# v2-carb-sync-shield.net
KiCad netlist of a schematic drawn in EAGLE
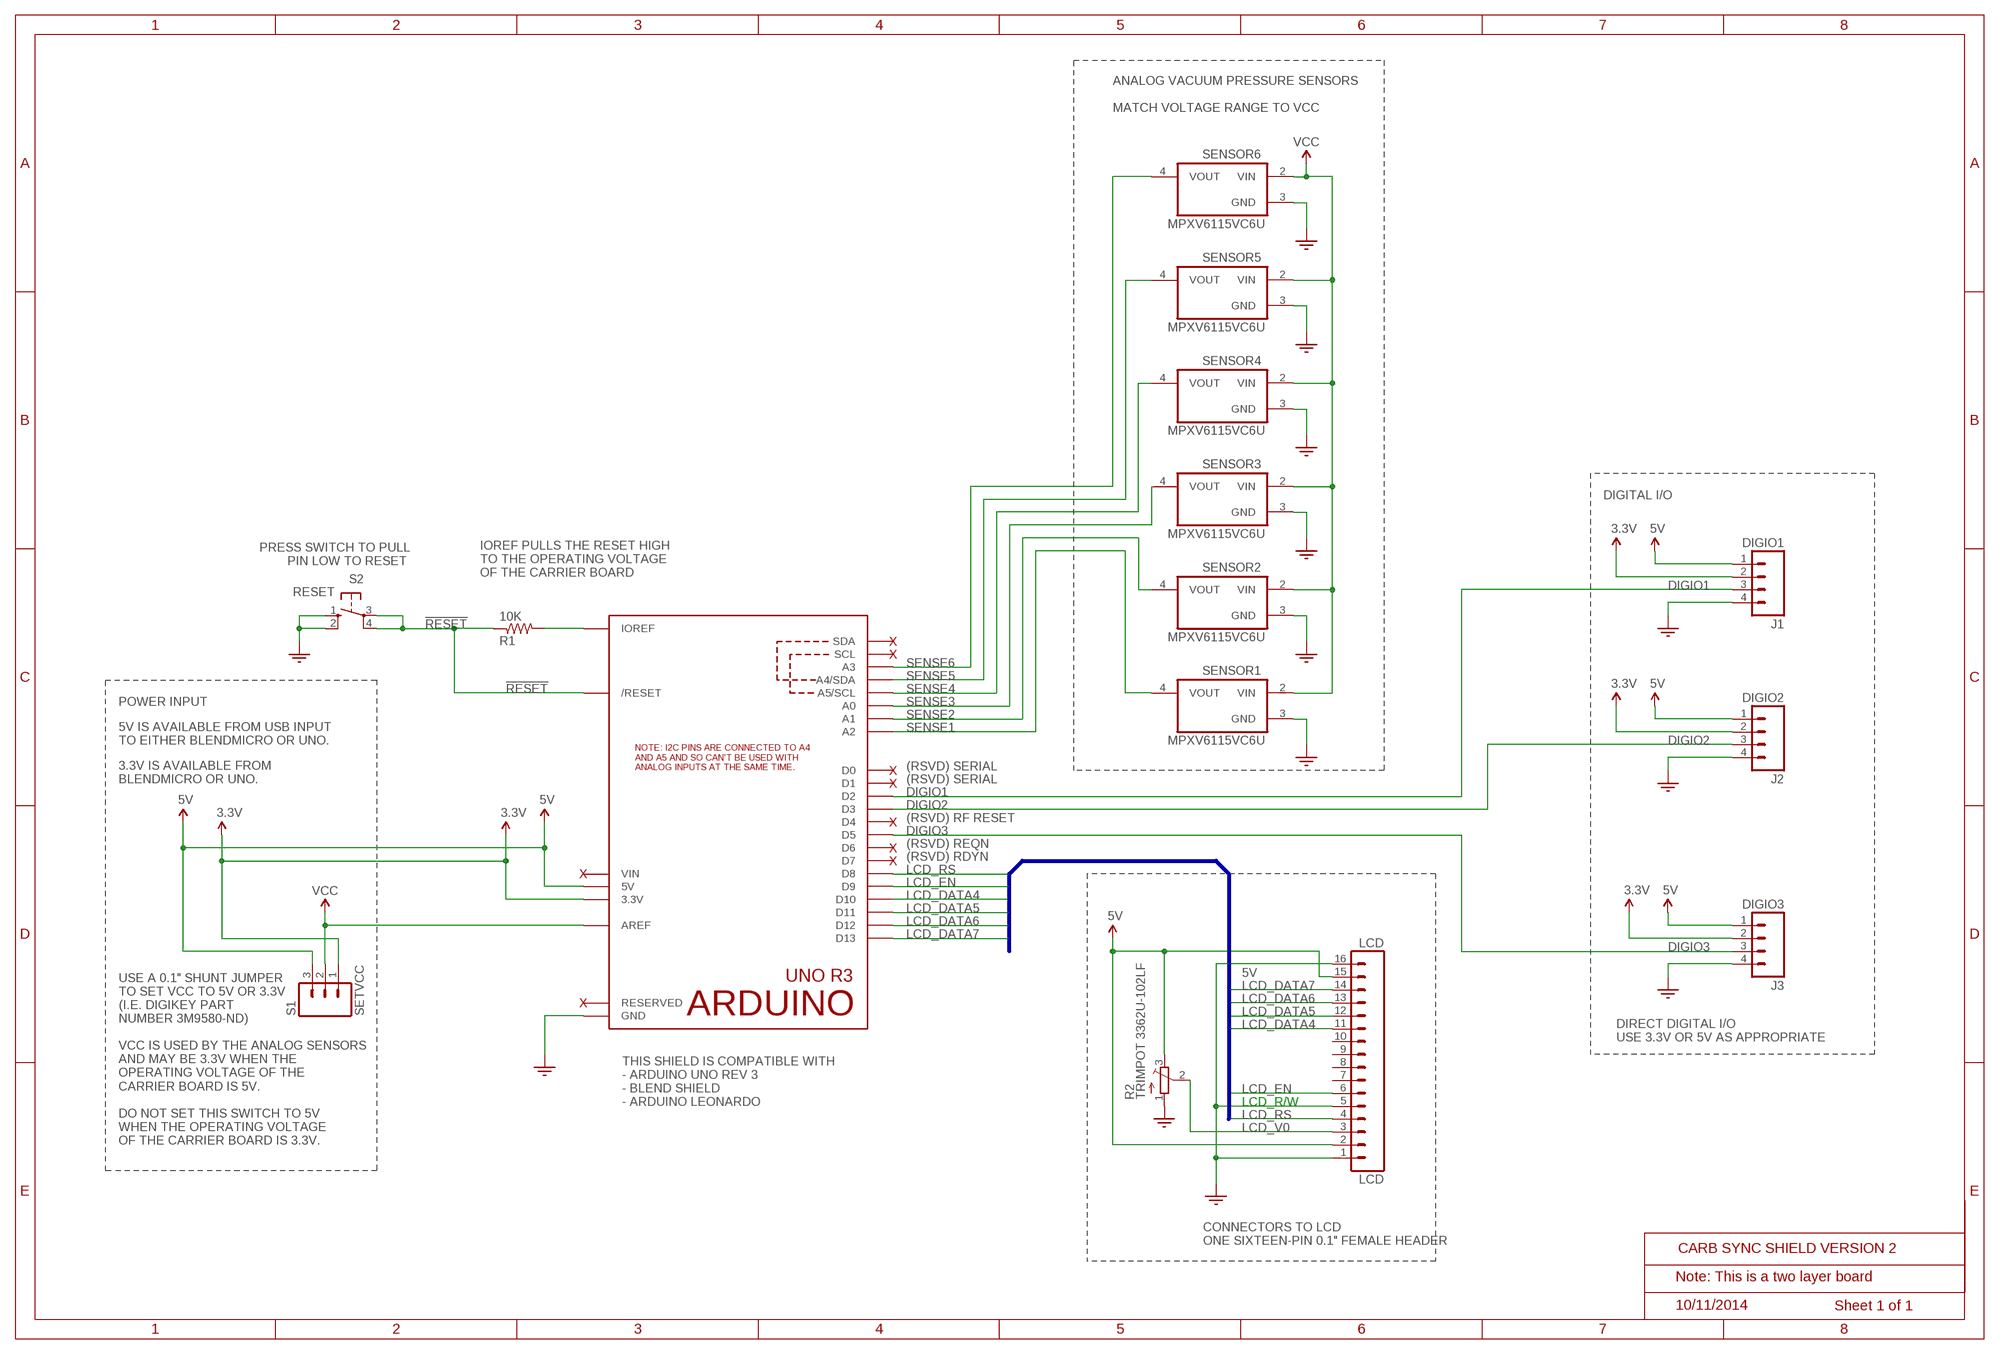
[diagram p0: schematic, sheet 1]

(export (version "E")
  (design (tool "Eeschema 10.0.6"))
  (components
    (comp (ref "J1")
      (value "DIGIO1")
      (footprint "eagle-import:1X04_LONGPADS")
      (libsource (lib "eagle-import") (part "M04LONGPADS"))
    )
    (comp (ref "J2")
      (value "DIGIO2")
      (footprint "eagle-import:1X04_LONGPADS")
      (libsource (lib "eagle-import") (part "M04LONGPADS"))
    )
    (comp (ref "J3")
      (value "DIGIO3")
      (footprint "eagle-import:1X04_LONGPADS")
      (libsource (lib "eagle-import") (part "M04LONGPADS"))
    )
    (comp (ref "LCD")
      (value "LCD")
      (footprint "eagle-import:CARBSYNCSHIELD_LCD")
      (libsource (lib "eagle-import") (part "CARBSYNCSHIELD_LCD"))
    )
    (comp (ref "R1")
      (value "10K")
      (footprint "eagle-import:0411_12")
      (libsource (lib "eagle-import") (part "R-US_0411/12"))
    )
    (comp (ref "R2")
      (value "TRIMPOT 3362U-102LF")
      (footprint "eagle-import:TRIM-3386")
      (libsource (lib "eagle-import") (part "TRIMPOT3386"))
    )
    (comp (ref "S1")
      (value "SETVCC")
      (footprint "eagle-import:1X03_LONGPADS")
      (libsource (lib "eagle-import") (part "M03LONGPADS"))
    )
    (comp (ref "S2")
      (value "RESET")
      (footprint "eagle-import:B3F-10XX")
      (fields (field (name "MPN") "B3F-1000"))
      (libsource (lib "eagle-import") (part "10-XX"))
    )
    (comp (ref "SENSOR1")
      (value "MPXV6115VC6U")
      (footprint "eagle-import:MPXV6115VC6U_T1-CASE482A")
      (libsource (lib "eagle-import") (part "MPXV6115VC6U"))
    )
    (comp (ref "SENSOR2")
      (value "MPXV6115VC6U")
      (footprint "eagle-import:MPXV6115VC6U_T1-CASE482A")
      (libsource (lib "eagle-import") (part "MPXV6115VC6U"))
    )
    (comp (ref "SENSOR3")
      (value "MPXV6115VC6U")
      (footprint "eagle-import:MPXV6115VC6U_T1-CASE482A")
      (libsource (lib "eagle-import") (part "MPXV6115VC6U"))
    )
    (comp (ref "SENSOR4")
      (value "MPXV6115VC6U")
      (footprint "eagle-import:MPXV6115VC6U_T1-CASE482A")
      (libsource (lib "eagle-import") (part "MPXV6115VC6U"))
    )
    (comp (ref "SENSOR5")
      (value "MPXV6115VC6U")
      (footprint "eagle-import:MPXV6115VC6U_T1-CASE482A")
      (libsource (lib "eagle-import") (part "MPXV6115VC6U"))
    )
    (comp (ref "SENSOR6")
      (value "MPXV6115VC6U")
      (footprint "eagle-import:MPXV6115VC6U_T1-CASE482A")
      (libsource (lib "eagle-import") (part "MPXV6115VC6U"))
    )
    (comp (ref "U$13")
      (value "ARDUINO-UNO-R3")
      (footprint "eagle-import:ARDUINO-UNO-R3-HOLES-NODIM")
      (libsource (lib "eagle-import") (part "ARDUINO-UNO-R3"))
    )
  )
  (nets
    (net (code "1") (name "/DIGIO1") (class "Default")
      (node (ref "J1") (pin "3") (pinfunction "3_3") (pintype "passive"))
      (node (ref "U$13") (pin "D2") (pinfunction "D2_D2") (pintype "bidirectional"))
    )
    (net (code "2") (name "/DIGIO2") (class "Default")
      (node (ref "J2") (pin "3") (pinfunction "3_3") (pintype "passive"))
      (node (ref "U$13") (pin "D3") (pinfunction "D3_D3") (pintype "bidirectional"))
    )
    (net (code "3") (name "/DIGIO3") (class "Default")
      (node (ref "J3") (pin "3") (pinfunction "3_3") (pintype "passive"))
      (node (ref "U$13") (pin "D5") (pinfunction "D5_D5") (pintype "bidirectional"))
    )
    (net (code "4") (name "/LCD_DATA4") (class "Default")
      (node (ref "LCD") (pin "11") (pinfunction "11_11") (pintype "passive"))
      (node (ref "U$13") (pin "D10") (pinfunction "D10_D10") (pintype "bidirectional"))
    )
    (net (code "5") (name "/LCD_DATA5") (class "Default")
      (node (ref "LCD") (pin "12") (pinfunction "12_12") (pintype "passive"))
      (node (ref "U$13") (pin "D11") (pinfunction "D11_D11") (pintype "bidirectional"))
    )
    (net (code "6") (name "/LCD_DATA6") (class "Default")
      (node (ref "LCD") (pin "13") (pinfunction "13_13") (pintype "passive"))
      (node (ref "U$13") (pin "D12") (pinfunction "D12_D12") (pintype "bidirectional"))
    )
    (net (code "7") (name "/LCD_DATA7") (class "Default")
      (node (ref "LCD") (pin "14") (pinfunction "14_14") (pintype "passive"))
      (node (ref "U$13") (pin "D13") (pinfunction "D13_D13") (pintype "bidirectional"))
    )
    (net (code "8") (name "/LCD_EN") (class "Default")
      (node (ref "LCD") (pin "6") (pinfunction "6_6") (pintype "passive"))
      (node (ref "U$13") (pin "D9") (pinfunction "D9_D9") (pintype "bidirectional"))
    )
    (net (code "9") (name "/LCD_RS") (class "Default")
      (node (ref "LCD") (pin "4") (pinfunction "4_4") (pintype "passive"))
      (node (ref "U$13") (pin "D8") (pinfunction "D8_D8") (pintype "bidirectional"))
    )
    (net (code "10") (name "/LCD_V0") (class "Default")
      (node (ref "LCD") (pin "3") (pinfunction "3_3") (pintype "passive"))
      (node (ref "R2") (pin "2") (pinfunction "S_2") (pintype "passive"))
    )
    (net (code "11") (name "/SENSE1") (class "Default")
      (node (ref "SENSOR1") (pin "4") (pinfunction "VOUT_4") (pintype "bidirectional"))
      (node (ref "U$13") (pin "A2") (pinfunction "A2_A2") (pintype "bidirectional"))
    )
    (net (code "12") (name "/SENSE2") (class "Default")
      (node (ref "SENSOR2") (pin "4") (pinfunction "VOUT_4") (pintype "bidirectional"))
      (node (ref "U$13") (pin "A1") (pinfunction "A1_A1") (pintype "bidirectional"))
    )
    (net (code "13") (name "/SENSE3") (class "Default")
      (node (ref "SENSOR3") (pin "4") (pinfunction "VOUT_4") (pintype "bidirectional"))
      (node (ref "U$13") (pin "A0") (pinfunction "A0_A0") (pintype "bidirectional"))
    )
    (net (code "14") (name "/SENSE4") (class "Default")
      (node (ref "SENSOR4") (pin "4") (pinfunction "VOUT_4") (pintype "bidirectional"))
      (node (ref "U$13") (pin "A5") (pinfunction "A5/SCL_A5") (pintype "bidirectional"))
    )
    (net (code "15") (name "/SENSE5") (class "Default")
      (node (ref "SENSOR5") (pin "4") (pinfunction "VOUT_4") (pintype "bidirectional"))
      (node (ref "U$13") (pin "A4") (pinfunction "A4/SDA_A4") (pintype "bidirectional"))
    )
    (net (code "16") (name "/SENSE6") (class "Default")
      (node (ref "SENSOR6") (pin "4") (pinfunction "VOUT_4") (pintype "bidirectional"))
      (node (ref "U$13") (pin "A3") (pinfunction "A3_A3") (pintype "bidirectional"))
    )
    (net (code "17") (name "/VIN") (class "Default")
      (node (ref "U$13") (pin "VIN") (pinfunction "VIN_VIN") (pintype "power_in"))
    )
    (net (code "18") (name "/~{RESET}") (class "Default")
      (node (ref "R1") (pin "1") (pinfunction "1_1") (pintype "passive"))
      (node (ref "S2") (pin "3") (pinfunction "P_3") (pintype "passive"))
      (node (ref "S2") (pin "4") (pinfunction "P1_4") (pintype "passive"))
      (node (ref "U$13") (pin "RESET") (pinfunction "/RESET_RESET") (pintype "bidirectional"))
    )
    (net (code "19") (name "3.3V") (class "Default")
      (node (ref "J1") (pin "2") (pinfunction "2_2") (pintype "passive"))
      (node (ref "J2") (pin "2") (pinfunction "2_2") (pintype "passive"))
      (node (ref "J3") (pin "2") (pinfunction "2_2") (pintype "passive"))
      (node (ref "S1") (pin "1") (pinfunction "1_1") (pintype "passive"))
      (node (ref "U$13") (pin "3V") (pinfunction "3.3V_3V") (pintype "power_in"))
    )
    (net (code "20") (name "5V") (class "Default")
      (node (ref "J1") (pin "1") (pinfunction "1_1") (pintype "passive"))
      (node (ref "J2") (pin "1") (pinfunction "1_1") (pintype "passive"))
      (node (ref "J3") (pin "1") (pinfunction "1_1") (pintype "passive"))
      (node (ref "LCD") (pin "15") (pinfunction "15_15") (pintype "passive"))
      (node (ref "LCD") (pin "2") (pinfunction "2_2") (pintype "passive"))
      (node (ref "R2") (pin "3") (pinfunction "E_3") (pintype "passive"))
      (node (ref "S1") (pin "3") (pinfunction "3_3") (pintype "passive"))
      (node (ref "U$13") (pin "5V") (pinfunction "5V_5V") (pintype "power_in"))
    )
    (net (code "21") (name "GND") (class "Default")
      (node (ref "J1") (pin "4") (pinfunction "4_4") (pintype "passive"))
      (node (ref "J2") (pin "4") (pinfunction "4_4") (pintype "passive"))
      (node (ref "J3") (pin "4") (pinfunction "4_4") (pintype "passive"))
      (node (ref "LCD") (pin "1") (pinfunction "1_1") (pintype "passive"))
      (node (ref "LCD") (pin "16") (pinfunction "16_16") (pintype "passive"))
      (node (ref "LCD") (pin "5") (pinfunction "5_5") (pintype "passive"))
      (node (ref "R2") (pin "1") (pinfunction "A_1") (pintype "passive"))
      (node (ref "S2") (pin "1") (pinfunction "S_1") (pintype "passive"))
      (node (ref "S2") (pin "2") (pinfunction "S1_2") (pintype "passive"))
      (node (ref "SENSOR1") (pin "3") (pinfunction "GND_3") (pintype "bidirectional"))
      (node (ref "SENSOR2") (pin "3") (pinfunction "GND_3") (pintype "bidirectional"))
      (node (ref "SENSOR3") (pin "3") (pinfunction "GND_3") (pintype "bidirectional"))
      (node (ref "SENSOR4") (pin "3") (pinfunction "GND_3") (pintype "bidirectional"))
      (node (ref "SENSOR5") (pin "3") (pinfunction "GND_3") (pintype "bidirectional"))
      (node (ref "SENSOR6") (pin "3") (pinfunction "GND_3") (pintype "bidirectional"))
      (node (ref "U$13") (pin "GND") (pinfunction "GND_GND") (pintype "power_in"))
      (node (ref "U$13") (pin "GND1") (pinfunction "GND_GND1") (pintype "power_in"))
      (node (ref "U$13") (pin "GND2") (pinfunction "GND_GND2") (pintype "power_in"))
    )
    (net (code "22") (name "Net-(R1-Pad2)") (class "Default")
      (node (ref "R1") (pin "2") (pinfunction "2_2") (pintype "passive"))
      (node (ref "U$13") (pin "IOREF") (pinfunction "IOREF_IOREF") (pintype "output"))
    )
    (net (code "23") (name "VCC") (class "Default")
      (node (ref "S1") (pin "2") (pinfunction "2_2") (pintype "passive"))
      (node (ref "SENSOR1") (pin "2") (pinfunction "VIN_2") (pintype "bidirectional"))
      (node (ref "SENSOR2") (pin "2") (pinfunction "VIN_2") (pintype "bidirectional"))
      (node (ref "SENSOR3") (pin "2") (pinfunction "VIN_2") (pintype "bidirectional"))
      (node (ref "SENSOR4") (pin "2") (pinfunction "VIN_2") (pintype "bidirectional"))
      (node (ref "SENSOR5") (pin "2") (pinfunction "VIN_2") (pintype "bidirectional"))
      (node (ref "SENSOR6") (pin "2") (pinfunction "VIN_2") (pintype "bidirectional"))
      (node (ref "U$13") (pin "AREF") (pinfunction "AREF_AREF") (pintype "bidirectional"))
    )
    (net (code "24") (name "unconnected-(LCD-Pad7)") (class "Default")
      (node (ref "LCD") (pin "7") (pinfunction "7_7") (pintype "passive"))
    )
    (net (code "25") (name "unconnected-(LCD-Pad8)") (class "Default")
      (node (ref "LCD") (pin "8") (pinfunction "8_8") (pintype "passive"))
    )
    (net (code "26") (name "unconnected-(LCD-Pad9)") (class "Default")
      (node (ref "LCD") (pin "9") (pinfunction "9_9") (pintype "passive"))
    )
    (net (code "27") (name "unconnected-(LCD-Pad10)") (class "Default")
      (node (ref "LCD") (pin "10") (pinfunction "10_10") (pintype "passive"))
    )
    (net (code "28") (name "unconnected-(U$13-PadD0)") (class "Default")
      (node (ref "U$13") (pin "D0") (pinfunction "D0_D0") (pintype "bidirectional"))
    )
    (net (code "29") (name "unconnected-(U$13-PadD1)") (class "Default")
      (node (ref "U$13") (pin "D1") (pinfunction "D1_D1") (pintype "bidirectional"))
    )
    (net (code "30") (name "unconnected-(U$13-PadD4)") (class "Default")
      (node (ref "U$13") (pin "D4") (pinfunction "D4_D4") (pintype "bidirectional"))
    )
    (net (code "31") (name "unconnected-(U$13-PadD6)") (class "Default")
      (node (ref "U$13") (pin "D6") (pinfunction "D6_D6") (pintype "bidirectional"))
    )
    (net (code "32") (name "unconnected-(U$13-PadD7)") (class "Default")
      (node (ref "U$13") (pin "D7") (pinfunction "D7_D7") (pintype "bidirectional"))
    )
    (net (code "33") (name "unconnected-(U$13-PadRESERVED)") (class "Default")
      (node (ref "U$13") (pin "RESERVED") (pinfunction "RESERVED_RESERVED") (pintype "no_connect"))
    )
    (net (code "34") (name "unconnected-(U$13-PadSCL)") (class "Default")
      (node (ref "U$13") (pin "SCL") (pinfunction "SCL_SCL") (pintype "bidirectional"))
    )
    (net (code "35") (name "unconnected-(U$13-PadSDA)") (class "Default")
      (node (ref "U$13") (pin "SDA") (pinfunction "SDA_SDA") (pintype "bidirectional"))
    )
  )
)
